# sensor-board.net
KiCad netlist of a schematic drawn in EAGLE
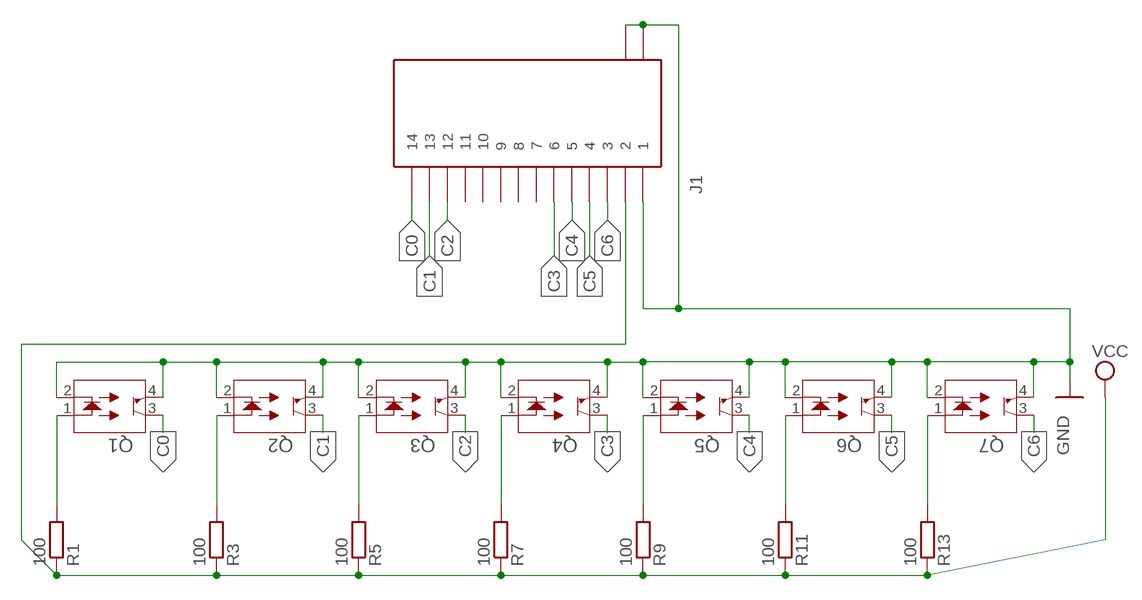
[diagram p0: schematic, sheet 1]

(export (version "E")
  (design (tool "Eeschema 10.0.6"))
  (components
    (comp (ref "J1")
      (value "686114148922")
      (footprint "eagle-import:686114148922")
      (fields (field (name "MOUSER_PART_NUMBER") "710-686114148922"))
      (libsource (lib "eagle-import") (part "686114148922"))
    )
    (comp (ref "Q1")
      (value "QRE1113")
      (footprint "eagle-import:DIP4_100AQ_ONS")
      (fields (field (name "COPYRIGHT") "Copyright (C) 2024 Ultra Librarian. All rights reserved."))
      (libsource (lib "eagle-import") (part "QRE1113"))
    )
    (comp (ref "Q2")
      (value "QRE1113")
      (footprint "eagle-import:DIP4_100AQ_ONS")
      (fields (field (name "COPYRIGHT") "Copyright (C) 2024 Ultra Librarian. All rights reserved."))
      (libsource (lib "eagle-import") (part "QRE1113"))
    )
    (comp (ref "Q3")
      (value "QRE1113")
      (footprint "eagle-import:DIP4_100AQ_ONS")
      (fields (field (name "COPYRIGHT") "Copyright (C) 2024 Ultra Librarian. All rights reserved."))
      (libsource (lib "eagle-import") (part "QRE1113"))
    )
    (comp (ref "Q4")
      (value "QRE1113")
      (footprint "eagle-import:DIP4_100AQ_ONS")
      (fields (field (name "COPYRIGHT") "Copyright (C) 2024 Ultra Librarian. All rights reserved."))
      (libsource (lib "eagle-import") (part "QRE1113"))
    )
    (comp (ref "Q5")
      (value "QRE1113")
      (footprint "eagle-import:DIP4_100AQ_ONS")
      (fields (field (name "COPYRIGHT") "Copyright (C) 2024 Ultra Librarian. All rights reserved."))
      (libsource (lib "eagle-import") (part "QRE1113"))
    )
    (comp (ref "Q6")
      (value "QRE1113")
      (footprint "eagle-import:DIP4_100AQ_ONS")
      (fields (field (name "COPYRIGHT") "Copyright (C) 2024 Ultra Librarian. All rights reserved."))
      (libsource (lib "eagle-import") (part "QRE1113"))
    )
    (comp (ref "Q7")
      (value "QRE1113")
      (footprint "eagle-import:DIP4_100AQ_ONS")
      (fields (field (name "COPYRIGHT") "Copyright (C) 2024 Ultra Librarian. All rights reserved."))
      (libsource (lib "eagle-import") (part "QRE1113"))
    )
    (comp (ref "R1")
      (value "100")
      (footprint "eagle-import:R0805")
      (libsource (lib "eagle-import") (part "R-EU_R0805"))
    )
    (comp (ref "R3")
      (value "100")
      (footprint "eagle-import:R0805")
      (libsource (lib "eagle-import") (part "R-EU_R0805"))
    )
    (comp (ref "R5")
      (value "100")
      (footprint "eagle-import:R0805")
      (libsource (lib "eagle-import") (part "R-EU_R0805"))
    )
    (comp (ref "R7")
      (value "100")
      (footprint "eagle-import:R0805")
      (libsource (lib "eagle-import") (part "R-EU_R0805"))
    )
    (comp (ref "R9")
      (value "100")
      (footprint "eagle-import:R0805")
      (libsource (lib "eagle-import") (part "R-EU_R0805"))
    )
    (comp (ref "R11")
      (value "100")
      (footprint "eagle-import:R0805")
      (libsource (lib "eagle-import") (part "R-EU_R0805"))
    )
    (comp (ref "R13")
      (value "100")
      (footprint "eagle-import:R0805")
      (libsource (lib "eagle-import") (part "R-EU_R0805"))
    )
  )
  (nets
    (net (code "1") (name "C0") (class "Default")
      (node (ref "J1") (pin "14") (pinfunction "14_14") (pintype "bidirectional"))
      (node (ref "Q1") (pin "3") (pinfunction "3_3") (pintype "passive"))
    )
    (net (code "2") (name "C1") (class "Default")
      (node (ref "J1") (pin "13") (pinfunction "13_13") (pintype "bidirectional"))
      (node (ref "Q2") (pin "3") (pinfunction "3_3") (pintype "passive"))
    )
    (net (code "3") (name "C2") (class "Default")
      (node (ref "J1") (pin "12") (pinfunction "12_12") (pintype "bidirectional"))
      (node (ref "Q3") (pin "3") (pinfunction "3_3") (pintype "passive"))
    )
    (net (code "4") (name "C3") (class "Default")
      (node (ref "J1") (pin "6") (pinfunction "6_6") (pintype "bidirectional"))
      (node (ref "Q4") (pin "3") (pinfunction "3_3") (pintype "passive"))
    )
    (net (code "5") (name "C4") (class "Default")
      (node (ref "J1") (pin "5") (pinfunction "5_5") (pintype "bidirectional"))
      (node (ref "Q5") (pin "3") (pinfunction "3_3") (pintype "passive"))
    )
    (net (code "6") (name "C5") (class "Default")
      (node (ref "J1") (pin "4") (pinfunction "4_4") (pintype "bidirectional"))
      (node (ref "Q6") (pin "3") (pinfunction "3_3") (pintype "passive"))
    )
    (net (code "7") (name "C6") (class "Default")
      (node (ref "J1") (pin "3") (pinfunction "3_3") (pintype "bidirectional"))
      (node (ref "Q7") (pin "3") (pinfunction "3_3") (pintype "passive"))
    )
    (net (code "8") (name "GND") (class "Default")
      (node (ref "J1") (pin "1") (pinfunction "1_1") (pintype "bidirectional"))
      (node (ref "J1") (pin "MP1") (pinfunction "MP1_MP1") (pintype "bidirectional"))
      (node (ref "J1") (pin "MP2") (pinfunction "MP2_MP2") (pintype "bidirectional"))
      (node (ref "Q1") (pin "2") (pinfunction "2_2") (pintype "passive"))
      (node (ref "Q1") (pin "4") (pinfunction "4_4") (pintype "passive"))
      (node (ref "Q2") (pin "2") (pinfunction "2_2") (pintype "passive"))
      (node (ref "Q2") (pin "4") (pinfunction "4_4") (pintype "passive"))
      (node (ref "Q3") (pin "2") (pinfunction "2_2") (pintype "passive"))
      (node (ref "Q3") (pin "4") (pinfunction "4_4") (pintype "passive"))
      (node (ref "Q4") (pin "2") (pinfunction "2_2") (pintype "passive"))
      (node (ref "Q4") (pin "4") (pinfunction "4_4") (pintype "passive"))
      (node (ref "Q5") (pin "2") (pinfunction "2_2") (pintype "passive"))
      (node (ref "Q5") (pin "4") (pinfunction "4_4") (pintype "passive"))
      (node (ref "Q6") (pin "2") (pinfunction "2_2") (pintype "passive"))
      (node (ref "Q6") (pin "4") (pinfunction "4_4") (pintype "passive"))
      (node (ref "Q7") (pin "2") (pinfunction "2_2") (pintype "passive"))
      (node (ref "Q7") (pin "4") (pinfunction "4_4") (pintype "passive"))
    )
    (net (code "9") (name "Net-(Q1-Pad1)") (class "Default")
      (node (ref "Q1") (pin "1") (pinfunction "1_1") (pintype "passive"))
      (node (ref "R1") (pin "2") (pinfunction "2_2") (pintype "passive"))
    )
    (net (code "10") (name "Net-(Q2-Pad1)") (class "Default")
      (node (ref "Q2") (pin "1") (pinfunction "1_1") (pintype "passive"))
      (node (ref "R3") (pin "2") (pinfunction "2_2") (pintype "passive"))
    )
    (net (code "11") (name "Net-(Q3-Pad1)") (class "Default")
      (node (ref "Q3") (pin "1") (pinfunction "1_1") (pintype "passive"))
      (node (ref "R5") (pin "2") (pinfunction "2_2") (pintype "passive"))
    )
    (net (code "12") (name "Net-(Q4-Pad1)") (class "Default")
      (node (ref "Q4") (pin "1") (pinfunction "1_1") (pintype "passive"))
      (node (ref "R7") (pin "2") (pinfunction "2_2") (pintype "passive"))
    )
    (net (code "13") (name "Net-(Q5-Pad1)") (class "Default")
      (node (ref "Q5") (pin "1") (pinfunction "1_1") (pintype "passive"))
      (node (ref "R9") (pin "2") (pinfunction "2_2") (pintype "passive"))
    )
    (net (code "14") (name "Net-(Q6-Pad1)") (class "Default")
      (node (ref "Q6") (pin "1") (pinfunction "1_1") (pintype "passive"))
      (node (ref "R11") (pin "2") (pinfunction "2_2") (pintype "passive"))
    )
    (net (code "15") (name "Net-(Q7-Pad1)") (class "Default")
      (node (ref "Q7") (pin "1") (pinfunction "1_1") (pintype "passive"))
      (node (ref "R13") (pin "2") (pinfunction "2_2") (pintype "passive"))
    )
    (net (code "16") (name "VCC") (class "Default")
      (node (ref "J1") (pin "2") (pinfunction "2_2") (pintype "bidirectional"))
      (node (ref "R1") (pin "1") (pinfunction "1_1") (pintype "passive"))
      (node (ref "R11") (pin "1") (pinfunction "1_1") (pintype "passive"))
      (node (ref "R13") (pin "1") (pinfunction "1_1") (pintype "passive"))
      (node (ref "R3") (pin "1") (pinfunction "1_1") (pintype "passive"))
      (node (ref "R5") (pin "1") (pinfunction "1_1") (pintype "passive"))
      (node (ref "R7") (pin "1") (pinfunction "1_1") (pintype "passive"))
      (node (ref "R9") (pin "1") (pinfunction "1_1") (pintype "passive"))
    )
    (net (code "17") (name "unconnected-(J1-Pad7)") (class "Default")
      (node (ref "J1") (pin "7") (pinfunction "7_7") (pintype "bidirectional"))
    )
    (net (code "18") (name "unconnected-(J1-Pad8)") (class "Default")
      (node (ref "J1") (pin "8") (pinfunction "8_8") (pintype "bidirectional"))
    )
    (net (code "19") (name "unconnected-(J1-Pad9)") (class "Default")
      (node (ref "J1") (pin "9") (pinfunction "9_9") (pintype "bidirectional"))
    )
    (net (code "20") (name "unconnected-(J1-Pad10)") (class "Default")
      (node (ref "J1") (pin "10") (pinfunction "10_10") (pintype "bidirectional"))
    )
    (net (code "21") (name "unconnected-(J1-Pad11)") (class "Default")
      (node (ref "J1") (pin "11") (pinfunction "11_11") (pintype "bidirectional"))
    )
  )
)
